# 01-PCIe.net
KiCad netlist of a schematic drawn in Altium Designer
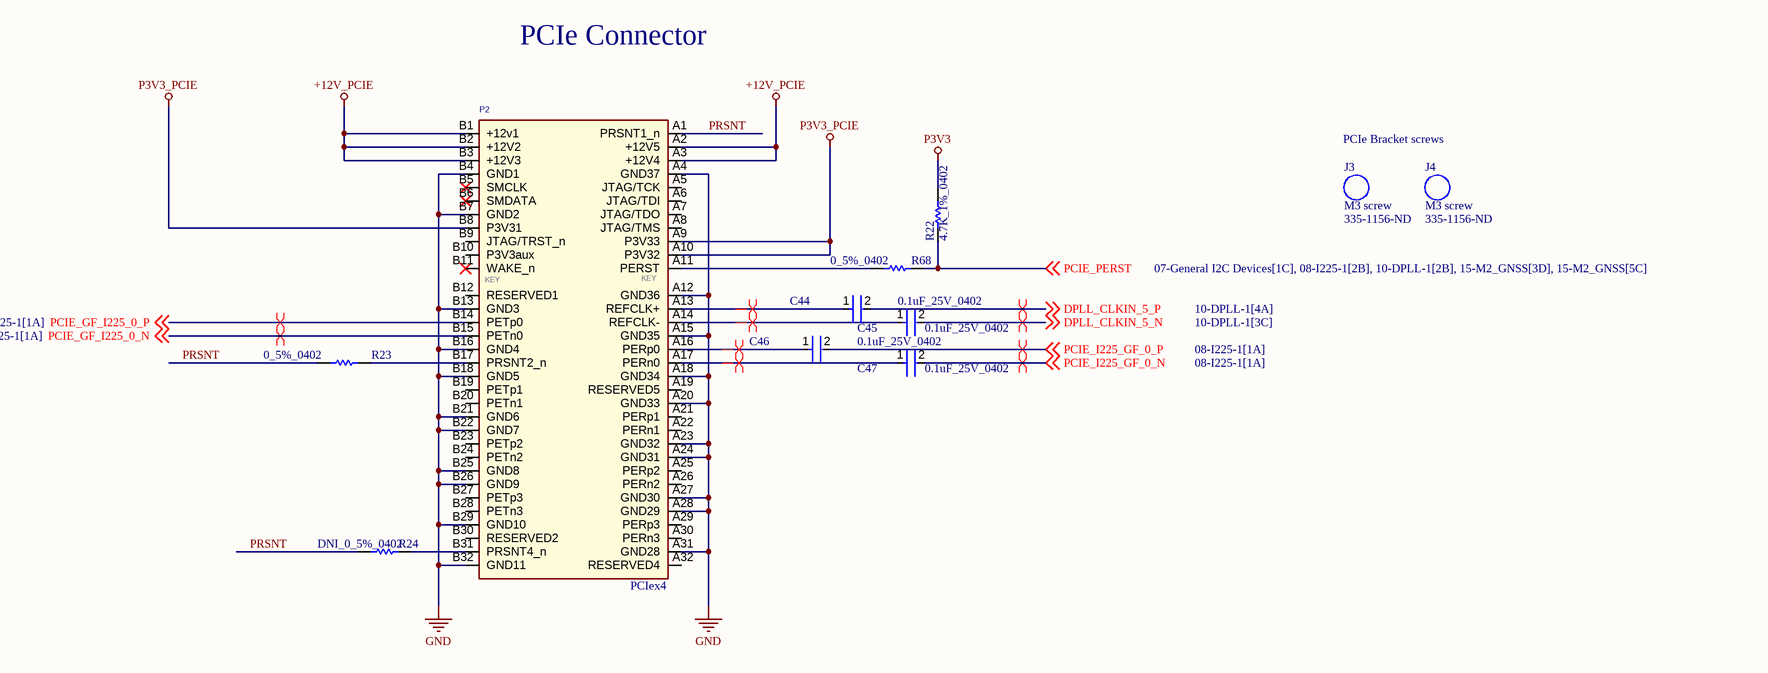
[diagram p0: 01-PCIe.SchDoc]

(export (version "E")
  (design (tool "Eeschema 10.0.6"))
  (components
    (comp (ref "C44")
      (value "0.1uF_25V_0402")
      (footprint "FP-0402-L_1_0_1-W_0_5_0_1-IPC_C")
      (description "General Purpose Ceramic Capacitor, 0402, 100nF, 10%, X7R, 15%, 25V")
      (fields (field (name "VOLTAGE") "25V") (field (name "TOLERANCE") "10%"))
      (libsource (lib "Altium Content Vault") (part "b4654b650e69147ec39a6b967a45e02"))
    )
    (comp (ref "C45")
      (value "0.1uF_25V_0402")
      (footprint "FP-0402-L_1_0_1-W_0_5_0_1-IPC_C")
      (description "General Purpose Ceramic Capacitor, 0402, 100nF, 10%, X7R, 15%, 25V")
      (fields (field (name "VOLTAGE") "25V") (field (name "TOLERANCE") "10%"))
      (libsource (lib "Altium Content Vault") (part "b4654b650e69147ec39a6b967a45e02"))
    )
    (comp (ref "C46")
      (value "0.1uF_25V_0402")
      (footprint "FP-0402-L_1_0_1-W_0_5_0_1-IPC_C")
      (description "General Purpose Ceramic Capacitor, 0402, 100nF, 10%, X7R, 15%, 25V")
      (fields (field (name "VOLTAGE") "25V") (field (name "TOLERANCE") "10%"))
      (libsource (lib "Altium Content Vault") (part "b4654b650e69147ec39a6b967a45e02"))
    )
    (comp (ref "C47")
      (value "0.1uF_25V_0402")
      (footprint "FP-0402-L_1_0_1-W_0_5_0_1-IPC_C")
      (description "General Purpose Ceramic Capacitor, 0402, 100nF, 10%, X7R, 15%, 25V")
      (fields (field (name "VOLTAGE") "25V") (field (name "TOLERANCE") "10%"))
      (libsource (lib "Altium Content Vault") (part "b4654b650e69147ec39a6b967a45e02"))
    )
    (comp (ref "J3")
      (value "M3 screw")
      (fields (field (name "SUPPLIER PART NUMBER 1") "335-1156-ND"))
      (libsource (lib "FPGA_CONN") (part "M3 screw"))
    )
    (comp (ref "J4")
      (value "M3 screw")
      (fields (field (name "SUPPLIER PART NUMBER 1") "335-1156-ND"))
      (libsource (lib "FPGA_CONN") (part "M3 screw"))
    )
    (comp (ref "P2")
      (value "PCIex4")
      (footprint "PCIE_4LANE_EDGE")
      (description "PCIE x4 Edge Connector,OrCAD Symbol,NC")
      (fields (field (name "PART NUMBER") "451") (field (name "MANUFACTURER") "NA"))
      (libsource (lib "Connectors") (part "PCIex4"))
    )
    (comp (ref "R22")
      (value "4.7K_1%_0402")
      (footprint "RESC1005X40X25NL10T10")
      (fields (field (name "MANUFACTURER") "Bourns") (field (name "PART NUMBER") "CR0402-FX-4701GLF"))
      (libsource (lib "Altium Content Vault") (part "RES"))
    )
    (comp (ref "R23")
      (value "0_5%_0402")
      (footprint "RESC1005X40X25LL10T10")
      (fields (field (name "MANUFACTURER") "KOA Speer") (field (name "PART NUMBER") "RK73Z1ETTP"))
      (libsource (lib "Altium Content Vault") (part "RES"))
    )
    (comp (ref "R24")
      (value "DNI_0_5%_0402")
      (footprint "RESC1005X40X25LL10T10")
      (fields (field (name "MANUFACTURER") "KOA Speer") (field (name "PART NUMBER") "RK73Z1ETTP"))
      (libsource (lib "Altium Content Vault") (part "RES"))
    )
    (comp (ref "R68")
      (value "0_5%_0402")
      (footprint "RESC1005X40X25LL10T10")
      (fields (field (name "MANUFACTURER") "KOA Speer") (field (name "PART NUMBER") "RK73Z1ETTP"))
      (libsource (lib "Altium Content Vault") (part "RES"))
    )
  )
  (nets
    (net (code "1") (name "+12V_PCIE") (class "Default")
      (node (ref "P2") (pin "A2") (pinfunction "+12V5_A2") (pintype "passive"))
      (node (ref "P2") (pin "A3") (pinfunction "+12V4_A3") (pintype "passive"))
      (node (ref "P2") (pin "B1") (pinfunction "+12v1_B1") (pintype "power_in"))
      (node (ref "P2") (pin "B2") (pinfunction "+12V2_B2") (pintype "power_in"))
      (node (ref "P2") (pin "B3") (pinfunction "+12V3_B3") (pintype "power_in"))
    )
    (net (code "2") (name "/PRSNT") (class "Default")
      (node (ref "P2") (pin "A1") (pinfunction "PRSNT1_n_A1") (pintype "passive"))
      (node (ref "R23") (pin "1") (pinfunction "1_1") (pintype "passive"))
      (node (ref "R24") (pin "1") (pinfunction "1_1") (pintype "passive"))
    )
    (net (code "3") (name "DPLL_CLKIN_5_N") (class "Default")
      (node (ref "C45") (pin "2") (pinfunction "2_2") (pintype "passive"))
    )
    (net (code "4") (name "DPLL_CLKIN_5_P") (class "Default")
      (node (ref "C44") (pin "2") (pinfunction "2_2") (pintype "passive"))
    )
    (net (code "5") (name "GND") (class "Default")
      (node (ref "P2") (pin "A12") (pinfunction "GND36_A12") (pintype "power_in"))
      (node (ref "P2") (pin "A15") (pinfunction "GND35_A15") (pintype "power_in"))
      (node (ref "P2") (pin "A18") (pinfunction "GND34_A18") (pintype "power_in"))
      (node (ref "P2") (pin "A20") (pinfunction "GND33_A20") (pintype "power_in"))
      (node (ref "P2") (pin "A23") (pinfunction "GND32_A23") (pintype "power_in"))
      (node (ref "P2") (pin "A24") (pinfunction "GND31_A24") (pintype "power_in"))
      (node (ref "P2") (pin "A27") (pinfunction "GND30_A27") (pintype "power_in"))
      (node (ref "P2") (pin "A28") (pinfunction "GND29_A28") (pintype "power_in"))
      (node (ref "P2") (pin "A31") (pinfunction "GND28_A31") (pintype "power_in"))
      (node (ref "P2") (pin "A4") (pinfunction "GND37_A4") (pintype "power_in"))
      (node (ref "P2") (pin "B13") (pinfunction "GND3_B13") (pintype "power_in"))
      (node (ref "P2") (pin "B16") (pinfunction "GND4_B16") (pintype "power_in"))
      (node (ref "P2") (pin "B18") (pinfunction "GND5_B18") (pintype "power_in"))
      (node (ref "P2") (pin "B21") (pinfunction "GND6_B21") (pintype "power_in"))
      (node (ref "P2") (pin "B22") (pinfunction "GND7_B22") (pintype "power_in"))
      (node (ref "P2") (pin "B25") (pinfunction "GND8_B25") (pintype "power_in"))
      (node (ref "P2") (pin "B26") (pinfunction "GND9_B26") (pintype "power_in"))
      (node (ref "P2") (pin "B29") (pinfunction "GND10_B29") (pintype "power_in"))
      (node (ref "P2") (pin "B32") (pinfunction "GND11_B32") (pintype "power_in"))
      (node (ref "P2") (pin "B4") (pinfunction "GND1_B4") (pintype "power_in"))
      (node (ref "P2") (pin "B7") (pinfunction "GND2_B7") (pintype "power_in"))
    )
    (net (code "6") (name "Net-(P2-PERST)") (class "Default")
      (node (ref "P2") (pin "A11") (pinfunction "PERST_A11") (pintype "passive"))
      (node (ref "R68") (pin "1") (pinfunction "1_1") (pintype "passive"))
    )
    (net (code "7") (name "Net-(P2-PERn0)") (class "Default")
      (node (ref "C47") (pin "1") (pinfunction "1_1") (pintype "passive"))
      (node (ref "P2") (pin "A17") (pinfunction "PERn0_A17") (pintype "passive"))
    )
    (net (code "8") (name "Net-(P2-PERp0)") (class "Default")
      (node (ref "C46") (pin "1") (pinfunction "1_1") (pintype "passive"))
      (node (ref "P2") (pin "A16") (pinfunction "PERp0_A16") (pintype "passive"))
    )
    (net (code "9") (name "Net-(P2-PRSNT2_n)") (class "Default")
      (node (ref "P2") (pin "B17") (pinfunction "PRSNT2_n_B17") (pintype "passive"))
      (node (ref "R23") (pin "2") (pinfunction "2_2") (pintype "passive"))
    )
    (net (code "10") (name "Net-(P2-PRSNT4_n)") (class "Default")
      (node (ref "P2") (pin "B31") (pinfunction "PRSNT4_n_B31") (pintype "passive"))
      (node (ref "R24") (pin "2") (pinfunction "2_2") (pintype "passive"))
    )
    (net (code "11") (name "Net-(P2-REFCLK+)") (class "Default")
      (node (ref "C44") (pin "1") (pinfunction "1_1") (pintype "passive"))
      (node (ref "P2") (pin "A13") (pinfunction "REFCLK+_A13") (pintype "passive"))
    )
    (net (code "12") (name "Net-(P2-REFCLK-)") (class "Default")
      (node (ref "C45") (pin "1") (pinfunction "1_1") (pintype "passive"))
      (node (ref "P2") (pin "A14") (pinfunction "REFCLK-_A14") (pintype "passive"))
    )
    (net (code "13") (name "P3V3") (class "Default")
      (node (ref "R22") (pin "2") (pinfunction "2_2") (pintype "passive"))
    )
    (net (code "14") (name "P3V3_PCIE") (class "Default")
      (node (ref "P2") (pin "A10") (pinfunction "P3V32_A10") (pintype "passive"))
      (node (ref "P2") (pin "A9") (pinfunction "P3V33_A9") (pintype "passive"))
      (node (ref "P2") (pin "B8") (pinfunction "P3V31_B8") (pintype "power_in"))
    )
    (net (code "15") (name "PCIE_GF_I225_0_N") (class "Default")
      (node (ref "P2") (pin "B15") (pinfunction "PETn0_B15") (pintype "passive"))
    )
    (net (code "16") (name "PCIE_GF_I225_0_P") (class "Default")
      (node (ref "P2") (pin "B14") (pinfunction "PETp0_B14") (pintype "passive"))
    )
    (net (code "17") (name "PCIE_I225_GF_0_N") (class "Default")
      (node (ref "C47") (pin "2") (pinfunction "2_2") (pintype "passive"))
    )
    (net (code "18") (name "PCIE_I225_GF_0_P") (class "Default")
      (node (ref "C46") (pin "2") (pinfunction "2_2") (pintype "passive"))
    )
    (net (code "19") (name "PCIE_PERST") (class "Default")
      (node (ref "R22") (pin "1") (pinfunction "1_1") (pintype "passive"))
      (node (ref "R68") (pin "2") (pinfunction "2_2") (pintype "passive"))
    )
    (net (code "20") (name "unconnected-(P2-JTAG{slash}TCK-PadA5)") (class "Default")
      (node (ref "P2") (pin "A5") (pinfunction "JTAG/TCK_A5") (pintype "passive"))
    )
    (net (code "21") (name "unconnected-(P2-JTAG{slash}TDI-PadA6)") (class "Default")
      (node (ref "P2") (pin "A6") (pinfunction "JTAG/TDI_A6") (pintype "passive"))
    )
    (net (code "22") (name "unconnected-(P2-JTAG{slash}TDO-PadA7)") (class "Default")
      (node (ref "P2") (pin "A7") (pinfunction "JTAG/TDO_A7") (pintype "passive"))
    )
    (net (code "23") (name "unconnected-(P2-JTAG{slash}TMS-PadA8)") (class "Default")
      (node (ref "P2") (pin "A8") (pinfunction "JTAG/TMS_A8") (pintype "passive"))
    )
    (net (code "24") (name "unconnected-(P2-JTAG{slash}TRST_n-PadB9)") (class "Default")
      (node (ref "P2") (pin "B9") (pinfunction "JTAG/TRST_n_B9") (pintype "passive"))
    )
    (net (code "25") (name "unconnected-(P2-P3V3aux-PadB10)") (class "Default")
      (node (ref "P2") (pin "B10") (pinfunction "P3V3aux_B10") (pintype "passive"))
    )
    (net (code "26") (name "unconnected-(P2-PERn1-PadA22)") (class "Default")
      (node (ref "P2") (pin "A22") (pinfunction "PERn1_A22") (pintype "passive"))
    )
    (net (code "27") (name "unconnected-(P2-PERn2-PadA26)") (class "Default")
      (node (ref "P2") (pin "A26") (pinfunction "PERn2_A26") (pintype "passive"))
    )
    (net (code "28") (name "unconnected-(P2-PERn3-PadA30)") (class "Default")
      (node (ref "P2") (pin "A30") (pinfunction "PERn3_A30") (pintype "passive"))
    )
    (net (code "29") (name "unconnected-(P2-PERp1-PadA21)") (class "Default")
      (node (ref "P2") (pin "A21") (pinfunction "PERp1_A21") (pintype "passive"))
    )
    (net (code "30") (name "unconnected-(P2-PERp2-PadA25)") (class "Default")
      (node (ref "P2") (pin "A25") (pinfunction "PERp2_A25") (pintype "passive"))
    )
    (net (code "31") (name "unconnected-(P2-PERp3-PadA29)") (class "Default")
      (node (ref "P2") (pin "A29") (pinfunction "PERp3_A29") (pintype "passive"))
    )
    (net (code "32") (name "unconnected-(P2-PETn1-PadB20)") (class "Default")
      (node (ref "P2") (pin "B20") (pinfunction "PETn1_B20") (pintype "passive"))
    )
    (net (code "33") (name "unconnected-(P2-PETn2-PadB24)") (class "Default")
      (node (ref "P2") (pin "B24") (pinfunction "PETn2_B24") (pintype "passive"))
    )
    (net (code "34") (name "unconnected-(P2-PETn3-PadB28)") (class "Default")
      (node (ref "P2") (pin "B28") (pinfunction "PETn3_B28") (pintype "passive"))
    )
    (net (code "35") (name "unconnected-(P2-PETp1-PadB19)") (class "Default")
      (node (ref "P2") (pin "B19") (pinfunction "PETp1_B19") (pintype "passive"))
    )
    (net (code "36") (name "unconnected-(P2-PETp2-PadB23)") (class "Default")
      (node (ref "P2") (pin "B23") (pinfunction "PETp2_B23") (pintype "passive"))
    )
    (net (code "37") (name "unconnected-(P2-PETp3-PadB27)") (class "Default")
      (node (ref "P2") (pin "B27") (pinfunction "PETp3_B27") (pintype "passive"))
    )
    (net (code "38") (name "unconnected-(P2-RESERVED1-PadB12)") (class "Default")
      (node (ref "P2") (pin "B12") (pinfunction "RESERVED1_B12") (pintype "passive"))
    )
    (net (code "39") (name "unconnected-(P2-RESERVED2-PadB30)") (class "Default")
      (node (ref "P2") (pin "B30") (pinfunction "RESERVED2_B30") (pintype "passive"))
    )
    (net (code "40") (name "unconnected-(P2-RESERVED4-PadA32)") (class "Default")
      (node (ref "P2") (pin "A32") (pinfunction "RESERVED4_A32") (pintype "passive"))
    )
    (net (code "41") (name "unconnected-(P2-RESERVED5-PadA19)") (class "Default")
      (node (ref "P2") (pin "A19") (pinfunction "RESERVED5_A19") (pintype "passive"))
    )
    (net (code "42") (name "unconnected-(P2-SMCLK-PadB5)") (class "Default")
      (node (ref "P2") (pin "B5") (pinfunction "SMCLK_B5") (pintype "passive+no_connect"))
    )
    (net (code "43") (name "unconnected-(P2-SMDATA-PadB6)") (class "Default")
      (node (ref "P2") (pin "B6") (pinfunction "SMDATA_B6") (pintype "passive+no_connect"))
    )
    (net (code "44") (name "unconnected-(P2-WAKE_n-PadB11)") (class "Default")
      (node (ref "P2") (pin "B11") (pinfunction "WAKE_n_B11") (pintype "passive+no_connect"))
    )
  )
)
